# Accelerometer.net
KiCad netlist of a schematic drawn in Altium Designer
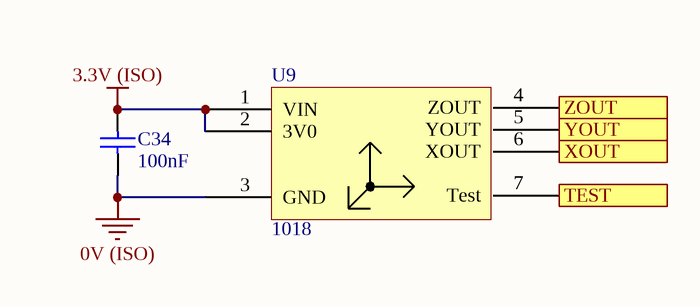
[diagram p0: Accelerometer.SchDoc]

(export (version "E")
  (design (tool "Eeschema 10.0.6"))
  (components
    (comp (ref "C34")
      (value "100nF")
      (footprint "0805")
      (fields
        (field (name "PART NUMBER") "GCM21BR71E104KA37L")
        (field (name "TOLERANCE") "10%")
        (field (name "MANUFACTURER") "muRata")
      )
      (libsource (lib "ts_20-standard-library") (part "Capacitor"))
    )
    (comp (ref "U9")
      (value "1018")
      (footprint "Adafruit 1018")
      (description "ADXL326 series Accelerometer, 3 Axis Sensor Evaluation Board")
      (fields (field (name "MANUFACTURER") "Adafruit"))
      (libsource (lib "ts_20-standard-library") (part "Adafruit 1018"))
    )
  )
  (nets
    (net (code "1") (name "/TEST") (class "Default")
      (node (ref "U9") (pin "7") (pinfunction "Test_7") (pintype "passive"))
    )
    (net (code "2") (name "/XOUT") (class "Default")
      (node (ref "U9") (pin "6") (pinfunction "XOUT_6") (pintype "passive"))
    )
    (net (code "3") (name "/YOUT") (class "Default")
      (node (ref "U9") (pin "5") (pinfunction "YOUT_5") (pintype "passive"))
    )
    (net (code "4") (name "/ZOUT") (class "Default")
      (node (ref "U9") (pin "4") (pinfunction "ZOUT_4") (pintype "passive"))
    )
    (net (code "5") (name "0V (ISO)") (class "Default")
      (node (ref "C34") (pin "1") (pinfunction "1_1") (pintype "passive"))
      (node (ref "U9") (pin "3") (pinfunction "GND_3") (pintype "passive"))
    )
    (net (code "6") (name "3.3V (ISO)") (class "Default")
      (node (ref "C34") (pin "2") (pinfunction "2_2") (pintype "passive"))
      (node (ref "U9") (pin "1") (pinfunction "VIN_1") (pintype "passive"))
      (node (ref "U9") (pin "2") (pinfunction "3V0_2") (pintype "passive"))
    )
  )
)
